# JOYSTICK_INTERFACE.net
KiCad netlist of a schematic drawn in EasyEDA
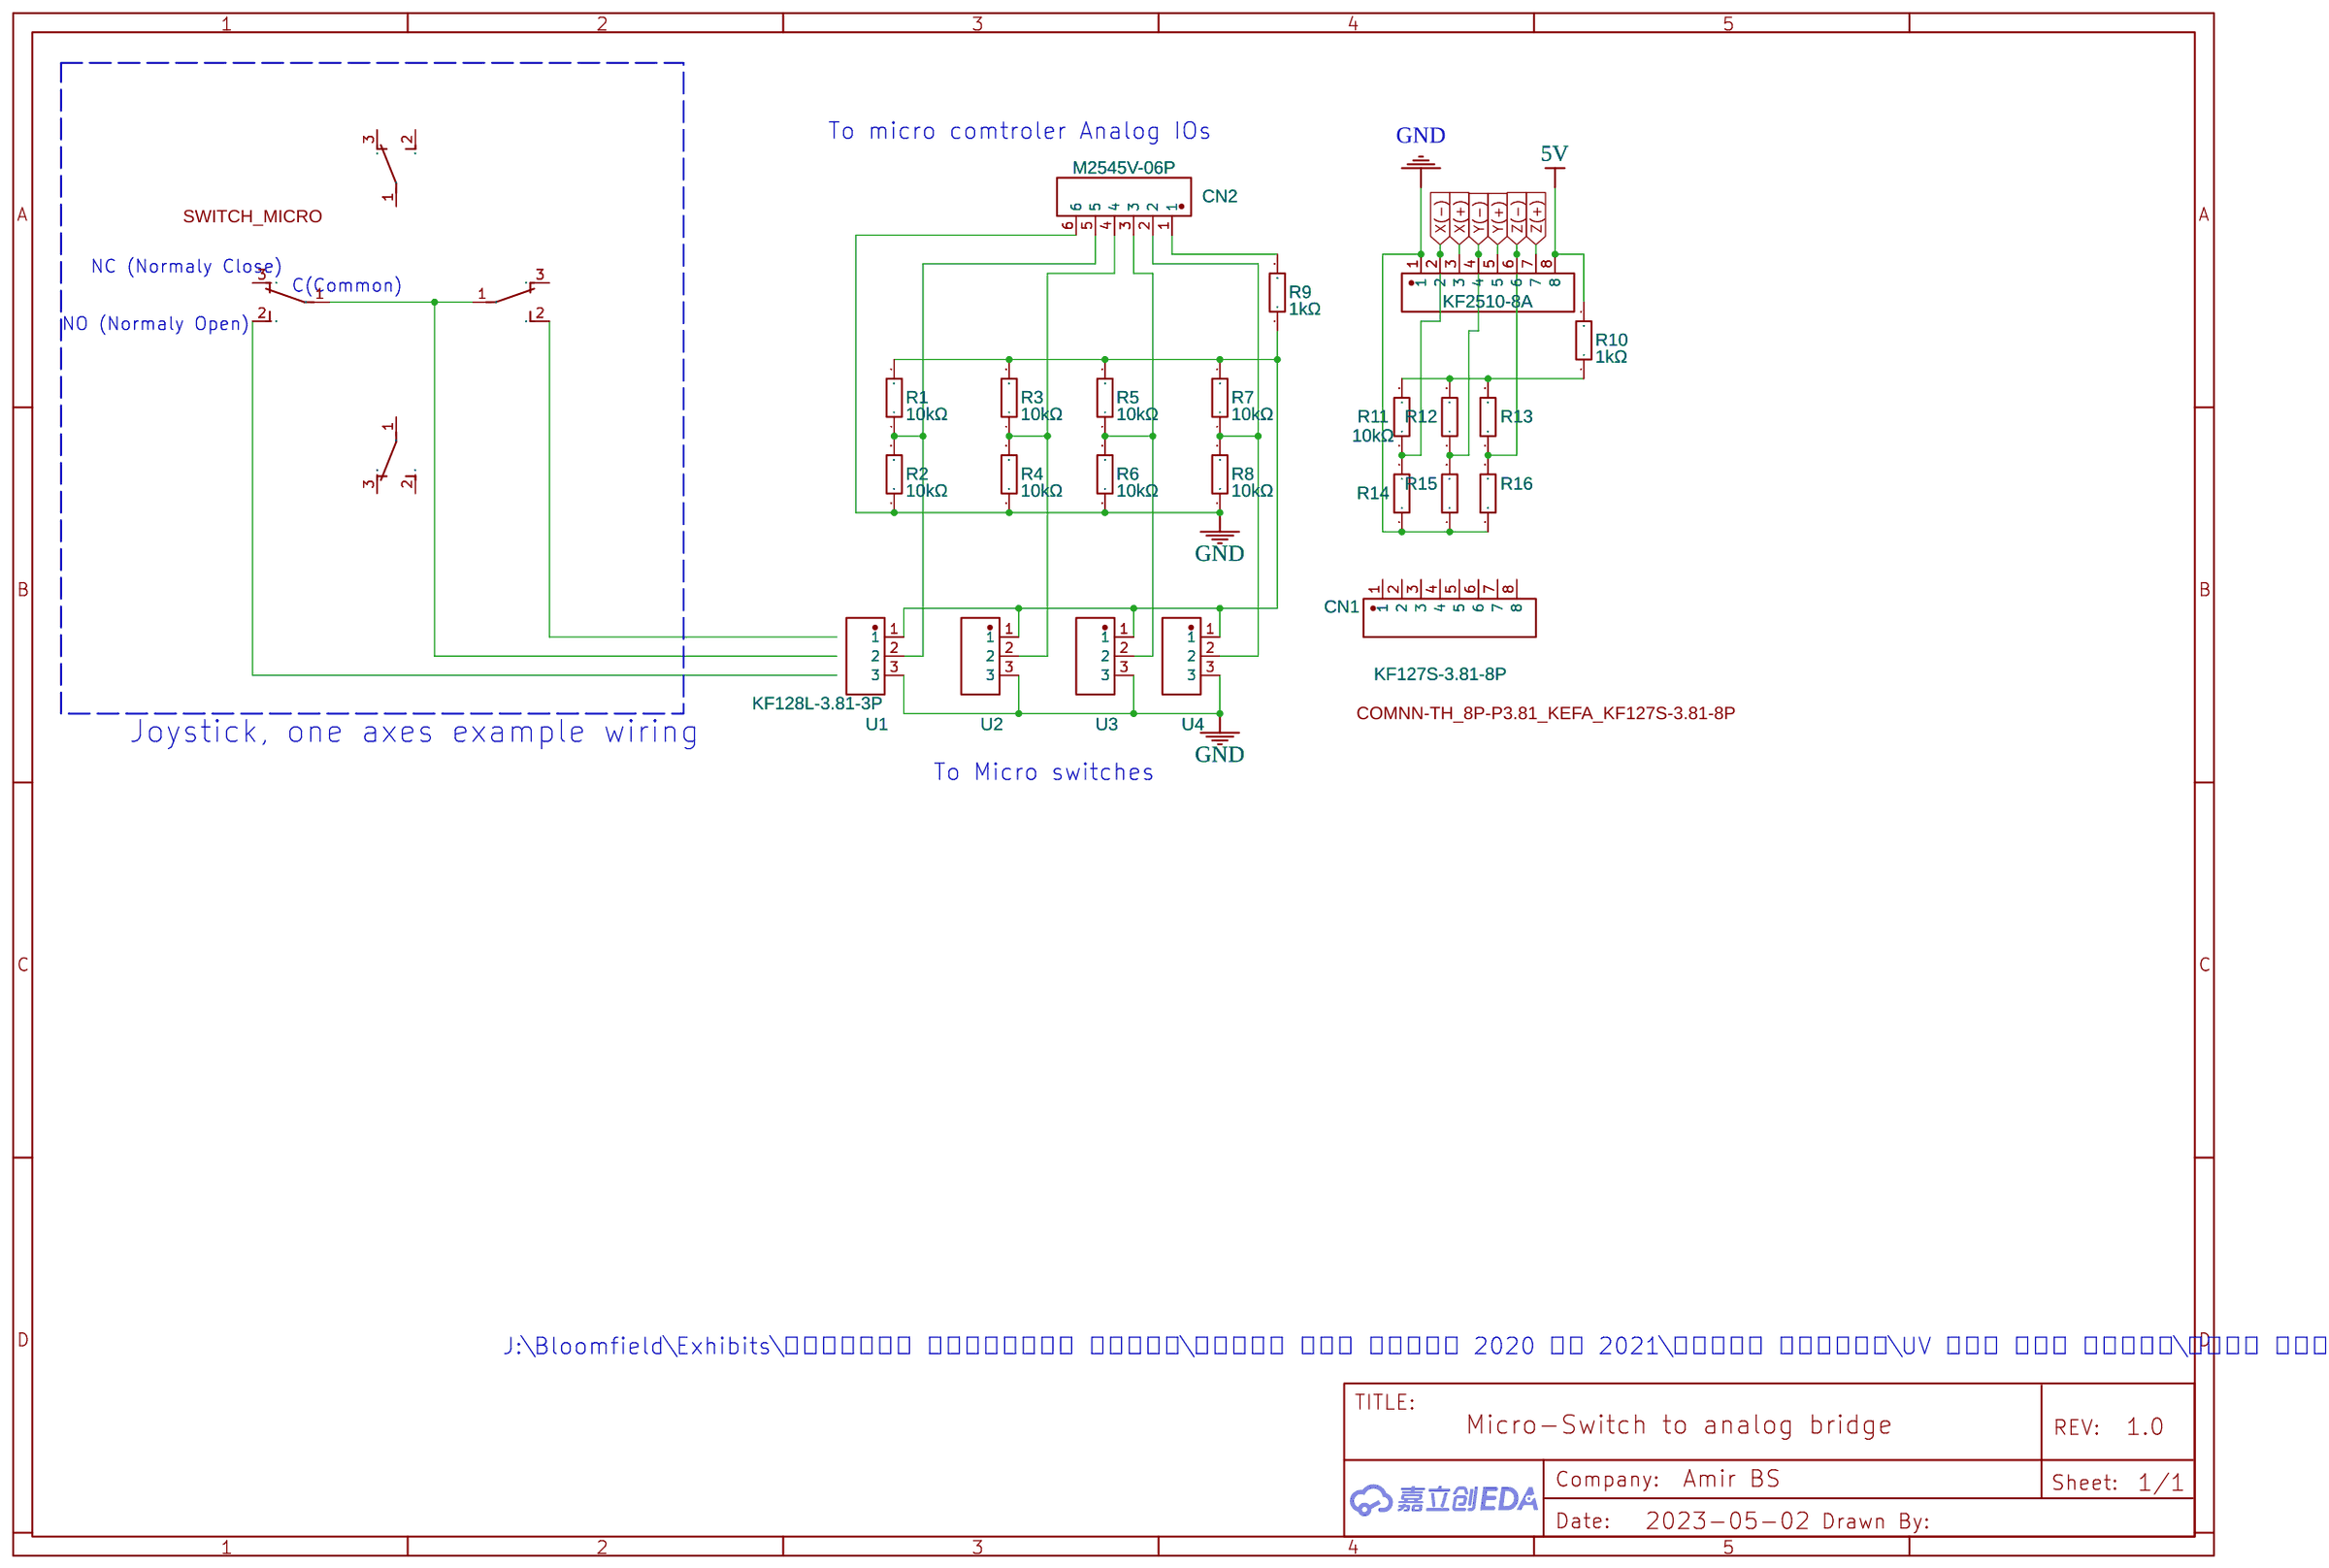
[diagram p0: schematic sheet]

(export (version "E")
  (design (tool "Eeschema 10.0.6"))
  (components
    (comp (ref "CN1")
      (value "KF127S-3.81-8P")
      (fields (field (name "Manufacturer") "KEFA(科发)"))
      (libsource (lib "") (part "KF127S-3.81-8P"))
    )
    (comp (ref "CN2")
      (value "M2545V-06P")
      (fields (field (name "BOM_Supplier Part") "C492454"))
      (libsource (lib "") (part "M2545V-06P"))
    )
    (comp (ref "CN3")
      (value "KF2510-8A")
      (fields (field (name "Manufacturer Part") "2510-8A") (field (name "Manufacturer") "BOOMELE(博穆精密)"))
      (libsource (lib "") (part "KF2510-8A"))
    )
    (comp (ref "R1")
      (value "10kΩ")
      (fields
        (field (name "BOM_Manufacturer Part") "0603WAF1002T5E")
        (field (name "BOM_Supplier Part") "C25804")
      )
      (libsource (lib "") (part "0603WAF1002T5E"))
    )
    (comp (ref "R2")
      (value "10kΩ")
      (fields
        (field (name "BOM_Manufacturer Part") "0603WAF1002T5E")
        (field (name "BOM_Supplier Part") "C25804")
      )
      (libsource (lib "") (part "0603WAF1002T5E"))
    )
    (comp (ref "R3")
      (value "10kΩ")
      (fields
        (field (name "BOM_Manufacturer Part") "0603WAF1002T5E")
        (field (name "BOM_Supplier Part") "C25804")
      )
      (libsource (lib "") (part "0603WAF1002T5E"))
    )
    (comp (ref "R4")
      (value "10kΩ")
      (fields
        (field (name "BOM_Manufacturer Part") "0603WAF1002T5E")
        (field (name "BOM_Supplier Part") "C25804")
      )
      (libsource (lib "") (part "0603WAF1002T5E"))
    )
    (comp (ref "R5")
      (value "10kΩ")
      (fields
        (field (name "BOM_Manufacturer Part") "0603WAF1002T5E")
        (field (name "BOM_Supplier Part") "C25804")
      )
      (libsource (lib "") (part "0603WAF1002T5E"))
    )
    (comp (ref "R6")
      (value "10kΩ")
      (fields
        (field (name "BOM_Manufacturer Part") "0603WAF1002T5E")
        (field (name "BOM_Supplier Part") "C25804")
      )
      (libsource (lib "") (part "0603WAF1002T5E"))
    )
    (comp (ref "R7")
      (value "10kΩ")
      (fields
        (field (name "BOM_Manufacturer Part") "0603WAF1002T5E")
        (field (name "BOM_Supplier Part") "C25804")
      )
      (libsource (lib "") (part "0603WAF1002T5E"))
    )
    (comp (ref "R8")
      (value "10kΩ")
      (fields
        (field (name "BOM_Manufacturer Part") "0603WAF1002T5E")
        (field (name "BOM_Supplier Part") "C25804")
      )
      (libsource (lib "") (part "0603WAF1002T5E"))
    )
    (comp (ref "R9")
      (value "1kΩ")
      (fields
        (field (name "BOM_Manufacturer Part") "0603WAF1001T5E")
        (field (name "BOM_Supplier Part") "C21190")
      )
      (libsource (lib "") (part "0603WAF1001T5E"))
    )
    (comp (ref "R10")
      (value "1kΩ")
      (fields
        (field (name "BOM_Manufacturer Part") "0603WAF1001T5E")
        (field (name "BOM_Supplier Part") "C21190")
      )
      (libsource (lib "") (part "0603WAF1001T5E"))
    )
    (comp (ref "R11")
      (value "10kΩ")
      (fields
        (field (name "BOM_Manufacturer Part") "0603WAF1002T5E")
        (field (name "BOM_Supplier Part") "C25804")
      )
      (libsource (lib "") (part "0603WAF1002T5E"))
    )
    (comp (ref "R12")
      (value "10kΩ")
      (fields
        (field (name "BOM_Manufacturer Part") "0603WAF1002T5E")
        (field (name "BOM_Supplier Part") "C25804")
      )
      (libsource (lib "") (part "0603WAF1002T5E"))
    )
    (comp (ref "R13")
      (value "10kΩ")
      (fields
        (field (name "BOM_Manufacturer Part") "0603WAF1002T5E")
        (field (name "BOM_Supplier Part") "C25804")
      )
      (libsource (lib "") (part "0603WAF1002T5E"))
    )
    (comp (ref "R14")
      (value "10kΩ")
      (fields
        (field (name "BOM_Manufacturer Part") "0603WAF1002T5E")
        (field (name "BOM_Supplier Part") "C25804")
      )
      (libsource (lib "") (part "0603WAF1002T5E"))
    )
    (comp (ref "R15")
      (value "10kΩ")
      (fields
        (field (name "BOM_Manufacturer Part") "0603WAF1002T5E")
        (field (name "BOM_Supplier Part") "C25804")
      )
      (libsource (lib "") (part "0603WAF1002T5E"))
    )
    (comp (ref "R16")
      (value "10kΩ")
      (fields
        (field (name "BOM_Manufacturer Part") "0603WAF1002T5E")
        (field (name "BOM_Supplier Part") "C25804")
      )
      (libsource (lib "") (part "0603WAF1002T5E"))
    )
    (comp (ref "S1") (value "MICRO SWITCH_3Pin") (libsource (lib "") (part "MICRO SWITCH_3Pin_1")))
    (comp (ref "S2") (value "MICRO SWITCH_3Pin") (libsource (lib "") (part "MICRO SWITCH_3Pin_2")))
    (comp (ref "S3") (value "MICRO SWITCH_3Pin") (libsource (lib "") (part "MICRO SWITCH_3Pin")))
    (comp (ref "S4") (value "MICRO SWITCH_3Pin") (libsource (lib "") (part "MICRO SWITCH_3Pin_3")))
    (comp (ref "U1")
      (value "KF128L-3.81-3P")
      (fields (field (name "BOM_Supplier Part") "C474933"))
      (libsource (lib "") (part "KF128L-3.81-3P"))
    )
    (comp (ref "U2")
      (value "KF128L-3.81-3P")
      (fields (field (name "BOM_Supplier Part") "C474933"))
      (libsource (lib "") (part "KF128L-3.81-3P"))
    )
    (comp (ref "U3")
      (value "KF128L-3.81-3P")
      (fields (field (name "BOM_Supplier Part") "C474933"))
      (libsource (lib "") (part "KF128L-3.81-3P"))
    )
    (comp (ref "U4")
      (value "KF128L-3.81-3P")
      (fields (field (name "BOM_Supplier Part") "C474933"))
      (libsource (lib "") (part "KF128L-3.81-3P"))
    )
  )
  (nets
    (net (code "1") (name "5V") (class "Default")
      (node (ref "CN3") (pin "8") (pinfunction "8_8") (pintype "unspecified"))
      (node (ref "R10") (pin "2") (pinfunction "2_2") (pintype "input"))
    )
    (net (code "2") (name "GND") (class "Default")
      (node (ref "CN2") (pin "6") (pinfunction "6_6") (pintype "unspecified"))
      (node (ref "CN3") (pin "1") (pinfunction "1_1") (pintype "unspecified"))
      (node (ref "R14") (pin "1") (pinfunction "1_1") (pintype "input"))
      (node (ref "R15") (pin "1") (pinfunction "1_1") (pintype "input"))
      (node (ref "R16") (pin "1") (pinfunction "1_1") (pintype "input"))
      (node (ref "R2") (pin "1") (pinfunction "1_1") (pintype "input"))
      (node (ref "R4") (pin "1") (pinfunction "1_1") (pintype "input"))
      (node (ref "R6") (pin "1") (pinfunction "1_1") (pintype "input"))
      (node (ref "R8") (pin "1") (pinfunction "1_1") (pintype "input"))
      (node (ref "U1") (pin "3") (pinfunction "3_3") (pintype "unspecified"))
      (node (ref "U2") (pin "3") (pinfunction "3_3") (pintype "unspecified"))
      (node (ref "U3") (pin "3") (pinfunction "3_3") (pintype "unspecified"))
      (node (ref "U4") (pin "3") (pinfunction "3_3") (pintype "unspecified"))
    )
    (net (code "3") (name "Net-(CN2-Pad1)") (class "Default")
      (node (ref "CN2") (pin "1") (pinfunction "1_1") (pintype "unspecified"))
      (node (ref "R9") (pin "2") (pinfunction "2_2") (pintype "input"))
    )
    (net (code "4") (name "Net-(CN2-Pad2)") (class "Default")
      (node (ref "CN2") (pin "2") (pinfunction "2_2") (pintype "unspecified"))
      (node (ref "R7") (pin "1") (pinfunction "1_1") (pintype "input"))
      (node (ref "R8") (pin "2") (pinfunction "2_2") (pintype "input"))
      (node (ref "U4") (pin "2") (pinfunction "2_2") (pintype "unspecified"))
    )
    (net (code "5") (name "Net-(CN2-Pad3)") (class "Default")
      (node (ref "CN2") (pin "3") (pinfunction "3_3") (pintype "unspecified"))
      (node (ref "R5") (pin "1") (pinfunction "1_1") (pintype "input"))
      (node (ref "R6") (pin "2") (pinfunction "2_2") (pintype "input"))
      (node (ref "U3") (pin "2") (pinfunction "2_2") (pintype "unspecified"))
    )
    (net (code "6") (name "Net-(CN2-Pad4)") (class "Default")
      (node (ref "CN2") (pin "4") (pinfunction "4_4") (pintype "unspecified"))
      (node (ref "R3") (pin "1") (pinfunction "1_1") (pintype "input"))
      (node (ref "R4") (pin "2") (pinfunction "2_2") (pintype "input"))
      (node (ref "U2") (pin "2") (pinfunction "2_2") (pintype "unspecified"))
    )
    (net (code "7") (name "Net-(CN2-Pad5)") (class "Default")
      (node (ref "CN2") (pin "5") (pinfunction "5_5") (pintype "unspecified"))
      (node (ref "R1") (pin "1") (pinfunction "1_1") (pintype "input"))
      (node (ref "R2") (pin "2") (pinfunction "2_2") (pintype "input"))
      (node (ref "U1") (pin "2") (pinfunction "2_2") (pintype "unspecified"))
    )
    (net (code "8") (name "Net-(R1-Pad2)") (class "Default")
      (node (ref "R1") (pin "2") (pinfunction "2_2") (pintype "input"))
      (node (ref "R3") (pin "2") (pinfunction "2_2") (pintype "input"))
      (node (ref "R5") (pin "2") (pinfunction "2_2") (pintype "input"))
      (node (ref "R7") (pin "2") (pinfunction "2_2") (pintype "input"))
      (node (ref "R9") (pin "1") (pinfunction "1_1") (pintype "input"))
      (node (ref "U1") (pin "1") (pinfunction "1_1") (pintype "unspecified"))
      (node (ref "U2") (pin "1") (pinfunction "1_1") (pintype "unspecified"))
      (node (ref "U3") (pin "1") (pinfunction "1_1") (pintype "unspecified"))
      (node (ref "U4") (pin "1") (pinfunction "1_1") (pintype "unspecified"))
    )
    (net (code "9") (name "Net-(R10-Pad1)") (class "Default")
      (node (ref "R10") (pin "1") (pinfunction "1_1") (pintype "input"))
      (node (ref "R11") (pin "2") (pinfunction "2_2") (pintype "input"))
      (node (ref "R12") (pin "2") (pinfunction "2_2") (pintype "input"))
      (node (ref "R13") (pin "2") (pinfunction "2_2") (pintype "input"))
    )
    (net (code "10") (name "Net-(S1-Pad1)") (class "Default")
      (node (ref "S1") (pin "1") (pinfunction "1_1") (pintype "bidirectional"))
      (node (ref "S2") (pin "1") (pinfunction "1_1") (pintype "bidirectional"))
    )
    (net (code "11") (name "X(+)") (class "Default")
      (node (ref "CN3") (pin "3") (pinfunction "3_3") (pintype "unspecified"))
    )
    (net (code "12") (name "X(-)") (class "Default")
      (node (ref "CN3") (pin "2") (pinfunction "2_2") (pintype "unspecified"))
      (node (ref "R11") (pin "1") (pinfunction "1_1") (pintype "input"))
      (node (ref "R14") (pin "2") (pinfunction "2_2") (pintype "input"))
    )
    (net (code "13") (name "Y(+)") (class "Default")
      (node (ref "CN3") (pin "5") (pinfunction "5_5") (pintype "unspecified"))
    )
    (net (code "14") (name "Y(-)") (class "Default")
      (node (ref "CN3") (pin "4") (pinfunction "4_4") (pintype "unspecified"))
      (node (ref "R12") (pin "1") (pinfunction "1_1") (pintype "input"))
      (node (ref "R15") (pin "2") (pinfunction "2_2") (pintype "input"))
    )
    (net (code "15") (name "Z(+)") (class "Default")
      (node (ref "CN3") (pin "7") (pinfunction "7_7") (pintype "unspecified"))
    )
    (net (code "16") (name "Z(-)") (class "Default")
      (node (ref "CN3") (pin "6") (pinfunction "6_6") (pintype "unspecified"))
      (node (ref "R13") (pin "1") (pinfunction "1_1") (pintype "input"))
      (node (ref "R16") (pin "2") (pinfunction "2_2") (pintype "input"))
    )
    (net (code "17") (name "unconnected-(CN1-Pad1)") (class "Default")
      (node (ref "CN1") (pin "1") (pinfunction "1_1") (pintype "unspecified"))
    )
    (net (code "18") (name "unconnected-(CN1-Pad2)") (class "Default")
      (node (ref "CN1") (pin "2") (pinfunction "2_2") (pintype "unspecified"))
    )
    (net (code "19") (name "unconnected-(CN1-Pad3)") (class "Default")
      (node (ref "CN1") (pin "3") (pinfunction "3_3") (pintype "unspecified"))
    )
    (net (code "20") (name "unconnected-(CN1-Pad4)") (class "Default")
      (node (ref "CN1") (pin "4") (pinfunction "4_4") (pintype "unspecified"))
    )
    (net (code "21") (name "unconnected-(CN1-Pad5)") (class "Default")
      (node (ref "CN1") (pin "5") (pinfunction "5_5") (pintype "unspecified"))
    )
    (net (code "22") (name "unconnected-(CN1-Pad6)") (class "Default")
      (node (ref "CN1") (pin "6") (pinfunction "6_6") (pintype "unspecified"))
    )
    (net (code "23") (name "unconnected-(CN1-Pad7)") (class "Default")
      (node (ref "CN1") (pin "7") (pinfunction "7_7") (pintype "unspecified"))
    )
    (net (code "24") (name "unconnected-(CN1-Pad8)") (class "Default")
      (node (ref "CN1") (pin "8") (pinfunction "8_8") (pintype "unspecified"))
    )
    (net (code "25") (name "unconnected-(S1-Pad2)") (class "Default")
      (node (ref "S1") (pin "2") (pinfunction "2_2") (pintype "bidirectional"))
    )
    (net (code "26") (name "unconnected-(S1-Pad3)") (class "Default")
      (node (ref "S1") (pin "3") (pinfunction "3_3") (pintype "bidirectional"))
    )
    (net (code "27") (name "unconnected-(S2-Pad2)") (class "Default")
      (node (ref "S2") (pin "2") (pinfunction "2_2") (pintype "bidirectional"))
    )
    (net (code "28") (name "unconnected-(S2-Pad3)") (class "Default")
      (node (ref "S2") (pin "3") (pinfunction "3_3") (pintype "bidirectional"))
    )
    (net (code "29") (name "unconnected-(S3-Pad1)") (class "Default")
      (node (ref "S3") (pin "1") (pinfunction "1_1") (pintype "bidirectional"))
    )
    (net (code "30") (name "unconnected-(S3-Pad2)") (class "Default")
      (node (ref "S3") (pin "2") (pinfunction "2_2") (pintype "bidirectional"))
    )
    (net (code "31") (name "unconnected-(S3-Pad3)") (class "Default")
      (node (ref "S3") (pin "3") (pinfunction "3_3") (pintype "bidirectional"))
    )
    (net (code "32") (name "unconnected-(S4-Pad1)") (class "Default")
      (node (ref "S4") (pin "1") (pinfunction "1_1") (pintype "bidirectional"))
    )
    (net (code "33") (name "unconnected-(S4-Pad2)") (class "Default")
      (node (ref "S4") (pin "2") (pinfunction "2_2") (pintype "bidirectional"))
    )
    (net (code "34") (name "unconnected-(S4-Pad3)") (class "Default")
      (node (ref "S4") (pin "3") (pinfunction "3_3") (pintype "bidirectional"))
    )
  )
)
